# SMPS_5V.net
KiCad netlist of a schematic drawn in Altium Designer
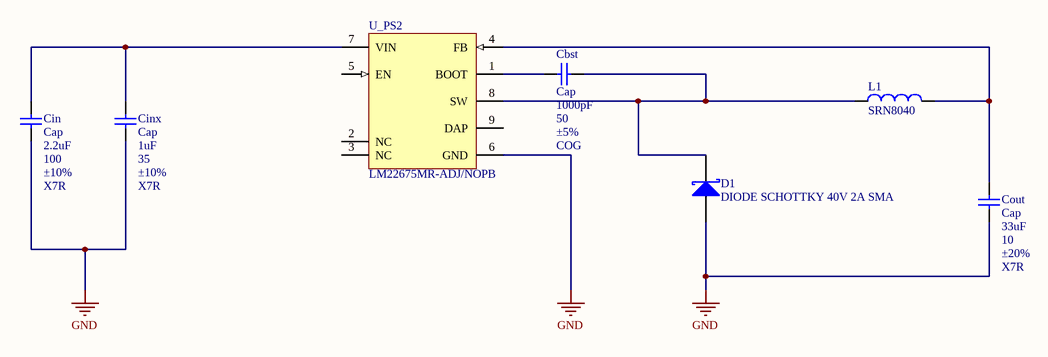
[diagram p0: SMPS_5V.SchDoc]

(export (version "E")
  (design (tool "Eeschema 10.0.6"))
  (components
    (comp (ref "Cbst")
      (value "Cap")
      (footprint "CAPC2012X09M")
      (description "CAP CER 1000pF 50v COG 0805")
      (fields
        (field (name "ALTIUM_VALUE") "1000pF")
        (field (name "WV") "50")
        (field (name "TOLERANCE") "±5%")
        (field (name "TYPE") "COG")
        (field (name "MPN") "C0805C102J5GACTU")
      )
      (libsource (lib "esd_library") (part "CAP-COG-1000pF-50V-±5%"))
    )
    (comp (ref "Cin")
      (value "Cap")
      (footprint "C1210")
      (description "CAP CER 2.2uF 100v X7R 1210")
      (fields
        (field (name "ALTIUM_VALUE") "2.2uF")
        (field (name "WV") "100")
        (field (name "TOLERANCE") "±10%")
        (field (name "TYPE") "X7R")
        (field (name "MPN") "C0805C225K4RACTU")
      )
      (libsource (lib "esd_library") (part "CAP-X7R-2.2uF-16V-±10%"))
    )
    (comp (ref "Cinx")
      (value "Cap")
      (footprint "CAPC2012X09M")
      (description "CAP CER 1uF 35v X7R 0805")
      (fields
        (field (name "ALTIUM_VALUE") "1uF")
        (field (name "WV") "35")
        (field (name "TOLERANCE") "±10%")
        (field (name "TYPE") "X7R")
        (field (name "MPN") "C0805C105K4RACTU")
      )
      (libsource (lib "esd_library") (part "CAP-X7R-1uF-16V-±10%"))
    )
    (comp (ref "Cout")
      (value "Cap")
      (footprint "C1210")
      (description "CAP CER 33uF 10v X5R 1210")
      (fields
        (field (name "ALTIUM_VALUE") "33uF")
        (field (name "WV") "10")
        (field (name "TOLERANCE") "±20%")
        (field (name "TYPE") "X7R")
        (field (name "MPN") "C0805C226M9PACTU")
      )
      (libsource (lib "esd_library") (part "CAP-X5R-22uF-6.3V-±20%"))
    )
    (comp (ref "D1")
      (value "DIODE SCHOTTKY 40V 2A SMA")
      (footprint "DIOM4326X23M")
      (description "Schottky Rectifier")
      (fields (field (name "MPN") "B240A-13-F"))
      (libsource (lib "esd_library") (part "DIODE SCHOTTKY 40V 2A SMA"))
    )
    (comp (ref "L1")
      (value "SRN8040")
      (footprint "INDP8080X40M")
      (description "FIXED IND 22UH 2.2A 100 MOHM SMD")
      (fields (field (name "MPN") "SRN8040-220M"))
      (libsource (lib "esd_library") (part "SRN8040"))
    )
    (comp (ref "U_PS2")
      (value "LM22675MR-ADJ/NOPB")
      (footprint "MRA08B_L")
      (description "1A SIMPLE SWITCHER®, Step-Down Voltage Regulator with Precision Enable, 8-pin PSOP, Pb-Free")
      (fields
        (field (name "MANUFACTURER") "National Semiconductor")
        (field (name "MPN") "LM22675MRE-ADJ/NOPB")
      )
      (libsource (lib "esd_library") (part "LM22675MR-ADJ/NOPB"))
    )
  )
  (nets
    (net (code "1") (name "GND") (class "Default")
      (node (ref "Cin") (pin "1") (pinfunction "1_1") (pintype "passive"))
      (node (ref "Cinx") (pin "1") (pinfunction "1_1") (pintype "passive"))
      (node (ref "Cout") (pin "1") (pinfunction "1_1") (pintype "passive"))
      (node (ref "D1") (pin "2") (pinfunction "A_2") (pintype "passive"))
      (node (ref "U_PS2") (pin "6") (pinfunction "GND_6") (pintype "power_in"))
    )
    (net (code "2") (name "Net-(D1-K)") (class "Default")
      (node (ref "Cbst") (pin "2") (pinfunction "2_2") (pintype "passive"))
      (node (ref "D1") (pin "1") (pinfunction "K_1") (pintype "passive"))
      (node (ref "L1") (pin "1") (pinfunction "1_1") (pintype "passive"))
      (node (ref "U_PS2") (pin "8") (pinfunction "SW_8") (pintype "power_in"))
    )
    (net (code "3") (name "Net-(U_PS2-BOOT)") (class "Default")
      (node (ref "Cbst") (pin "1") (pinfunction "1_1") (pintype "passive"))
      (node (ref "U_PS2") (pin "1") (pinfunction "BOOT_1") (pintype "passive"))
    )
    (net (code "4") (name "Net-(U_PS2-FB)") (class "Default")
      (node (ref "Cout") (pin "2") (pinfunction "2_2") (pintype "passive"))
      (node (ref "L1") (pin "2") (pinfunction "2_2") (pintype "passive"))
      (node (ref "U_PS2") (pin "4") (pinfunction "FB_4") (pintype "input"))
    )
    (net (code "5") (name "Net-(U_PS2-VIN)") (class "Default")
      (node (ref "Cin") (pin "2") (pinfunction "2_2") (pintype "passive"))
      (node (ref "Cinx") (pin "2") (pinfunction "2_2") (pintype "passive"))
      (node (ref "U_PS2") (pin "7") (pinfunction "VIN_7") (pintype "power_in"))
    )
    (net (code "6") (name "unconnected-(U_PS2-DAP-Pad9)") (class "Default")
      (node (ref "U_PS2") (pin "9") (pinfunction "DAP_9") (pintype "power_in"))
    )
    (net (code "7") (name "unconnected-(U_PS2-EN-Pad5)") (class "Default")
      (node (ref "U_PS2") (pin "5") (pinfunction "EN_5") (pintype "input"))
    )
    (net (code "8") (name "unconnected-(U_PS2-NC-Pad2)") (class "Default")
      (node (ref "U_PS2") (pin "2") (pinfunction "NC_2") (pintype "passive"))
    )
    (net (code "9") (name "unconnected-(U_PS2-NC-Pad3)") (class "Default")
      (node (ref "U_PS2") (pin "3") (pinfunction "NC_3") (pintype "passive"))
    )
  )
)
